# motordriver-v4_0_power-stage.net
KiCad netlist of a schematic drawn in Altium Designer
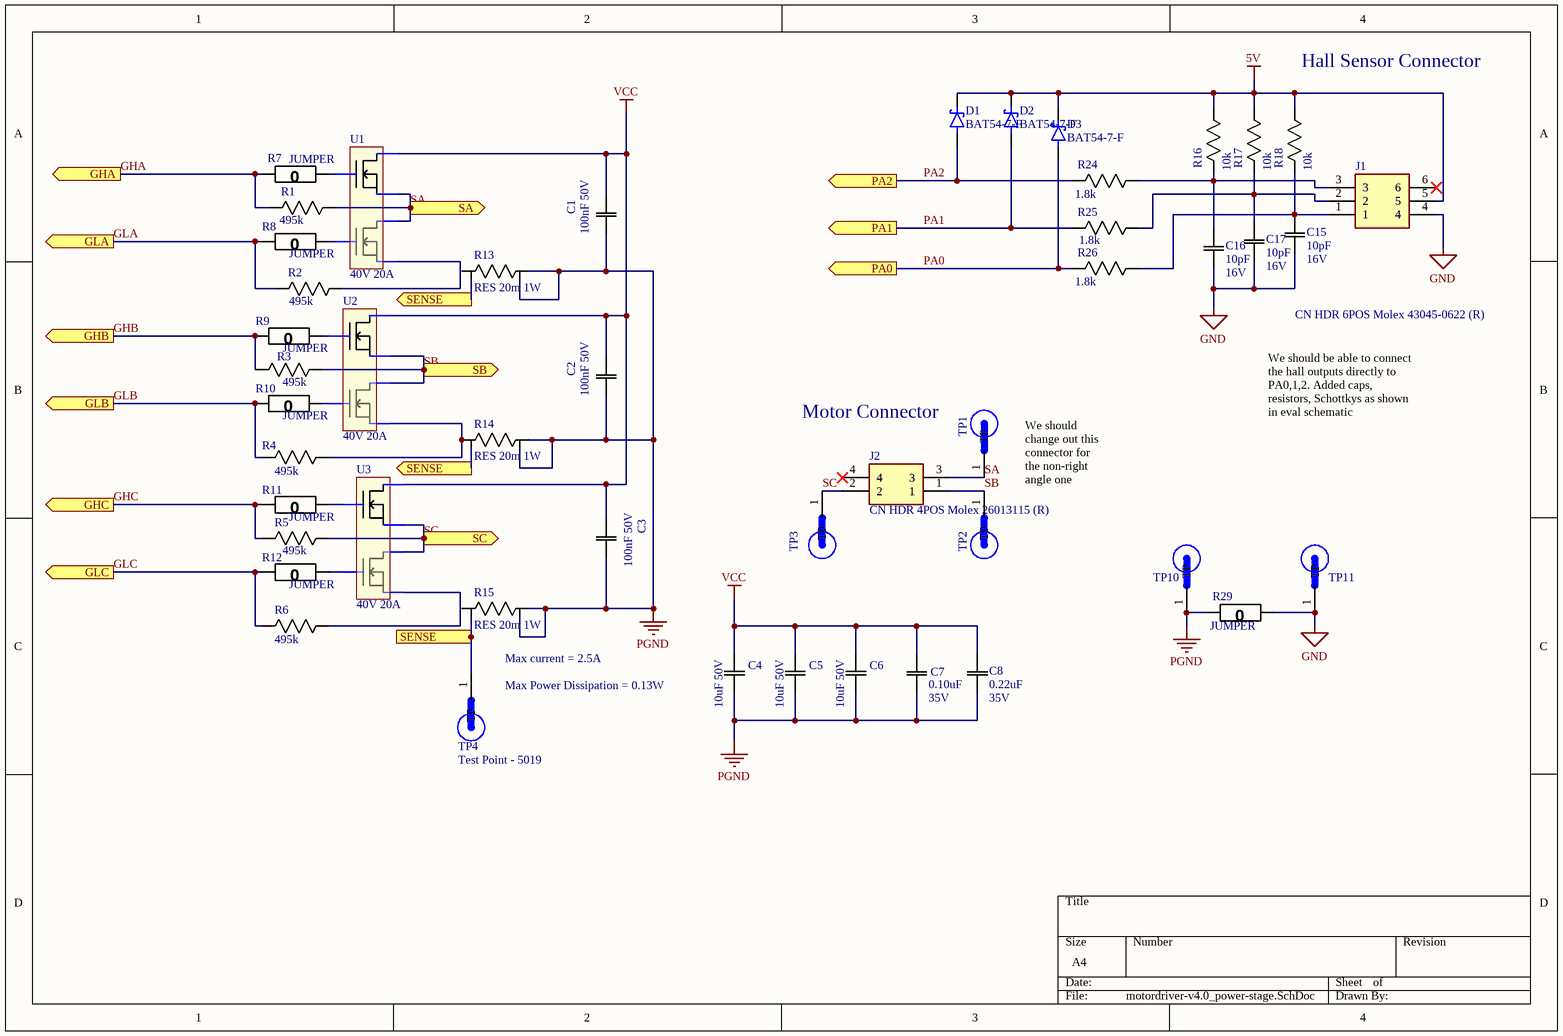
[diagram p0: motordriver-v4.0_power-stage.SchDoc]

(export (version "E")
  (design (tool "Eeschema 10.0.6"))
  (components
    (comp (ref "C1")
      (value "100nF 50V")
      (footprint "0603")
      (description "CAP CER 0.1UF 50V X7R 0805")
      (fields (field (name "TOLERANCE") "10%"))
      (libsource (lib "AltiumLibraries") (part "CAP 100nF 50V"))
    )
    (comp (ref "C2")
      (value "100nF 50V")
      (footprint "0603")
      (description "CAP CER 0.1UF 50V X7R 0805")
      (fields (field (name "TOLERANCE") "10%"))
      (libsource (lib "AltiumLibraries") (part "CAP 100nF 50V"))
    )
    (comp (ref "C3")
      (value "100nF 50V")
      (footprint "0603")
      (description "CAP CER 0.1UF 50V X7R 0805")
      (fields (field (name "TOLERANCE") "10%"))
      (libsource (lib "AltiumLibraries") (part "CAP 100nF 50V"))
    )
    (comp (ref "C4")
      (value "10uF 50V")
      (footprint "0805")
      (description "CAP CER 10UF 50V X7R")
      (fields (field (name "TOLERANCE") "10%"))
      (libsource (lib "AltiumLibraries") (part "CAP 10uF 50V"))
    )
    (comp (ref "C5")
      (value "10uF 50V")
      (footprint "0805")
      (description "CAP CER 10UF 50V X7R")
      (fields (field (name "TOLERANCE") "10%"))
      (libsource (lib "AltiumLibraries") (part "CAP 10uF 50V"))
    )
    (comp (ref "C6")
      (value "10uF 50V")
      (footprint "0805")
      (description "CAP CER 10UF 50V X7R")
      (fields (field (name "TOLERANCE") "10%"))
      (libsource (lib "AltiumLibraries") (part "CAP 10uF 50V"))
    )
    (comp (ref "C7")
      (value "0.10uF")
      (footprint "0603")
      (description "CAP CER 0.10UF 35V X7R 0603/0805")
      (fields (field (name "TOLERANCE") "10%") (field (name "RATING") "35V"))
      (libsource (lib "AltiumLibraries") (part "CAP 0.10uF 35V"))
    )
    (comp (ref "C8")
      (value "0.22uF")
      (footprint "0603")
      (description "CAP CER 0.22UF 35V X7R 0603/0805")
      (fields (field (name "TOLERANCE") "10%") (field (name "RATING") "35V"))
      (libsource (lib "AltiumLibraries") (part "CAP 0.22uF 35V"))
    )
    (comp (ref "C15")
      (value "10pF")
      (footprint "0603")
      (description "CAP CER 10PF 16V X5R 0603")
      (fields (field (name "TOLERANCE") "10%") (field (name "RATING") "16V"))
      (libsource (lib "AltiumLibraries") (part "CAP 10pF 16V"))
    )
    (comp (ref "C16")
      (value "10pF")
      (footprint "0603")
      (description "CAP CER 10PF 16V X5R 0603")
      (fields (field (name "TOLERANCE") "10%") (field (name "RATING") "16V"))
      (libsource (lib "AltiumLibraries") (part "CAP 10pF 16V"))
    )
    (comp (ref "C17")
      (value "10pF")
      (footprint "0603")
      (description "CAP CER 10PF 16V X5R 0603")
      (fields (field (name "TOLERANCE") "10%") (field (name "RATING") "16V"))
      (libsource (lib "AltiumLibraries") (part "CAP 10pF 16V"))
    )
    (comp (ref "D1")
      (value "BAT54-7-F")
      (footprint "BAT54-7-F")
      (description "DIODE SCHOTTKY 30V 200MA SOT23-3")
      (fields (field (name "MANUFACTURER") "Diodes Incorporated"))
      (libsource (lib "AltiumLibraries") (part "DIODE SCHOTTKY BAT54-7-F"))
    )
    (comp (ref "D2")
      (value "BAT54-7-F")
      (footprint "BAT54-7-F")
      (description "DIODE SCHOTTKY 30V 200MA SOT23-3")
      (fields (field (name "MANUFACTURER") "Diodes Incorporated"))
      (libsource (lib "AltiumLibraries") (part "DIODE SCHOTTKY BAT54-7-F"))
    )
    (comp (ref "D3")
      (value "BAT54-7-F")
      (footprint "BAT54-7-F")
      (description "DIODE SCHOTTKY 30V 200MA SOT23-3")
      (fields (field (name "MANUFACTURER") "Diodes Incorporated"))
      (libsource (lib "AltiumLibraries") (part "DIODE SCHOTTKY BAT54-7-F"))
    )
    (comp (ref "J1")
      (value "CN HDR 6POS Molex 43045-0622 (R)")
      (footprint "430450622")
      (description "Molex 43045-0622 6POS Microfit\r\ndual row, right angle")
      (libsource (lib "AltiumLibraries") (part "CN HDR 6POS Molex 43045-0622 (R)"))
    )
    (comp (ref "J2")
      (value "CN HDR 4POS Molex 26013115 (R)")
      (footprint "26013115")
      (description "Molex 26013115 4POS Minifit\r\ndual row, right angle")
      (libsource (lib "AltiumLibraries") (part "CN HDR 4POS Molex 26013115 (R)"))
    )
    (comp (ref "R1")
      (value "495k")
      (footprint "0603")
      (description "RES SMD 499K OHM 1% 1/8W 0805")
      (fields
        (field (name "MANUFACTURER") "Yageo")
        (field (name "MANUFACTURER PART NUMBER") "RC0805FR-07499KL")
      )
      (libsource (lib "AltiumLibraries") (part "RES 495k 1/8W"))
    )
    (comp (ref "R2")
      (value "495k")
      (footprint "0603")
      (description "RES SMD 499K OHM 1% 1/8W 0805")
      (fields
        (field (name "MANUFACTURER") "Yageo")
        (field (name "MANUFACTURER PART NUMBER") "RC0805FR-07499KL")
      )
      (libsource (lib "AltiumLibraries") (part "RES 495k 1/8W"))
    )
    (comp (ref "R3")
      (value "495k")
      (footprint "0603")
      (description "RES SMD 499K OHM 1% 1/8W 0805")
      (fields
        (field (name "MANUFACTURER") "Yageo")
        (field (name "MANUFACTURER PART NUMBER") "RC0805FR-07499KL")
      )
      (libsource (lib "AltiumLibraries") (part "RES 495k 1/8W"))
    )
    (comp (ref "R4")
      (value "495k")
      (footprint "0603")
      (description "RES SMD 499K OHM 1% 1/8W 0805")
      (fields
        (field (name "MANUFACTURER") "Yageo")
        (field (name "MANUFACTURER PART NUMBER") "RC0805FR-07499KL")
      )
      (libsource (lib "AltiumLibraries") (part "RES 495k 1/8W"))
    )
    (comp (ref "R5")
      (value "495k")
      (footprint "0603")
      (description "RES SMD 499K OHM 1% 1/8W 0805")
      (fields
        (field (name "MANUFACTURER") "Yageo")
        (field (name "MANUFACTURER PART NUMBER") "RC0805FR-07499KL")
      )
      (libsource (lib "AltiumLibraries") (part "RES 495k 1/8W"))
    )
    (comp (ref "R6")
      (value "495k")
      (footprint "0603")
      (description "RES SMD 499K OHM 1% 1/8W 0805")
      (fields
        (field (name "MANUFACTURER") "Yageo")
        (field (name "MANUFACTURER PART NUMBER") "RC0805FR-07499KL")
      )
      (libsource (lib "AltiumLibraries") (part "RES 495k 1/8W"))
    )
    (comp (ref "R7")
      (value "JUMPER")
      (footprint "0603")
      (description "RES SMD 0 OHM JUMPER GENERIC 0805")
      (libsource (lib "AltiumLibraries") (part "RES 0 JUMPER"))
    )
    (comp (ref "R8")
      (value "JUMPER")
      (footprint "0603")
      (description "RES SMD 0 OHM JUMPER GENERIC 0805")
      (libsource (lib "AltiumLibraries") (part "RES 0 JUMPER"))
    )
    (comp (ref "R9")
      (value "JUMPER")
      (footprint "0603")
      (description "RES SMD 0 OHM JUMPER GENERIC 0805")
      (libsource (lib "AltiumLibraries") (part "RES 0 JUMPER"))
    )
    (comp (ref "R10")
      (value "JUMPER")
      (footprint "0603")
      (description "RES SMD 0 OHM JUMPER GENERIC 0805")
      (libsource (lib "AltiumLibraries") (part "RES 0 JUMPER"))
    )
    (comp (ref "R11")
      (value "JUMPER")
      (footprint "0603")
      (description "RES SMD 0 OHM JUMPER GENERIC 0805")
      (libsource (lib "AltiumLibraries") (part "RES 0 JUMPER"))
    )
    (comp (ref "R12")
      (value "JUMPER")
      (footprint "0603")
      (description "RES SMD 0 OHM JUMPER GENERIC 0805")
      (libsource (lib "AltiumLibraries") (part "RES 0 JUMPER"))
    )
    (comp (ref "R13")
      (value "RES 20m 1W")
      (footprint "1206 - Sense")
      (description "RES SMD 0.02 OHM 1% 1W 1206")
      (libsource (lib "AltiumLibraries") (part "RES 20m 1W"))
    )
    (comp (ref "R14")
      (value "RES 20m 1W")
      (footprint "1206 - Sense")
      (description "RES SMD 0.02 OHM 1% 1W 1206")
      (libsource (lib "AltiumLibraries") (part "RES 20m 1W"))
    )
    (comp (ref "R15")
      (value "RES 20m 1W")
      (footprint "1206 - Sense")
      (description "RES SMD 0.02 OHM 1% 1W 1206")
      (libsource (lib "AltiumLibraries") (part "RES 20m 1W"))
    )
    (comp (ref "R16")
      (value "10k")
      (footprint "0603")
      (description "RES SMD 10K OHM 1% 1/8W 0805")
      (fields (field (name "TOLERANCE") "1%"))
      (libsource (lib "AltiumLibraries") (part "RES 10k 1/8W - 1%"))
    )
    (comp (ref "R17")
      (value "10k")
      (footprint "0603")
      (description "RES SMD 10K OHM 1% 1/8W 0805")
      (fields (field (name "TOLERANCE") "1%"))
      (libsource (lib "") (part "RES 10k 1/8W - 1%_1"))
    )
    (comp (ref "R18")
      (value "10k")
      (footprint "0603")
      (description "RES SMD 10K OHM 1% 1/8W 0805")
      (fields (field (name "TOLERANCE") "1%"))
      (libsource (lib "") (part "RES 10k 1/8W - 1%_1"))
    )
    (comp (ref "R24")
      (value "1.8k")
      (footprint "0603")
      (description "RES SMD 1.8K OHM 5% 1/8W 0805")
      (fields (field (name "TOLERANCE") "5%"))
      (libsource (lib "AltiumLibraries") (part "RES 1.8k 1/8W"))
    )
    (comp (ref "R25")
      (value "1.8k")
      (footprint "0603")
      (description "RES SMD 1.8K OHM 5% 1/8W 0805")
      (fields (field (name "TOLERANCE") "5%"))
      (libsource (lib "AltiumLibraries") (part "RES 1.8k 1/8W"))
    )
    (comp (ref "R26")
      (value "1.8k")
      (footprint "0603")
      (description "RES SMD 1.8K OHM 5% 1/8W 0805")
      (fields (field (name "TOLERANCE") "5%"))
      (libsource (lib "AltiumLibraries") (part "RES 1.8k 1/8W"))
    )
    (comp (ref "R29")
      (value "JUMPER")
      (footprint "0603")
      (description "RES SMD 0 OHM JUMPER GENERIC 0805")
      (libsource (lib "AltiumLibraries") (part "RES 0 JUMPER"))
    )
    (comp (ref "TP1")
      (value "Test Point - 5019")
      (footprint "TP380X203")
      (description "PC Test Point, Miniature Phosphor Bronze, Silver Plating Surface Mount Mounting Type")
      (fields (field (name "MP") "5019") (field (name "MF") "Keystone Electronics"))
      (libsource (lib "AltiumLibraries") (part "Test Point - 5019"))
    )
    (comp (ref "TP2")
      (value "Test Point - 5019")
      (footprint "TP380X203")
      (description "PC Test Point, Miniature Phosphor Bronze, Silver Plating Surface Mount Mounting Type")
      (fields (field (name "MP") "5019") (field (name "MF") "Keystone Electronics"))
      (libsource (lib "AltiumLibraries") (part "Test Point - 5019"))
    )
    (comp (ref "TP3")
      (value "Test Point - 5019")
      (footprint "TP380X203")
      (description "PC Test Point, Miniature Phosphor Bronze, Silver Plating Surface Mount Mounting Type")
      (fields (field (name "MP") "5019") (field (name "MF") "Keystone Electronics"))
      (libsource (lib "AltiumLibraries") (part "Test Point - 5019"))
    )
    (comp (ref "TP4")
      (value "Test Point - 5019")
      (footprint "TP380X203")
      (description "PC Test Point, Miniature Phosphor Bronze, Silver Plating Surface Mount Mounting Type")
      (fields (field (name "MP") "5019") (field (name "MF") "Keystone Electronics"))
      (libsource (lib "AltiumLibraries") (part "Test Point - 5019"))
    )
    (comp (ref "TP10")
      (value "Test Point - 5019")
      (footprint "TP380X203")
      (description "PC Test Point, Miniature Phosphor Bronze, Silver Plating Surface Mount Mounting Type")
      (fields (field (name "MP") "5019") (field (name "MF") "Keystone Electronics"))
      (libsource (lib "AltiumLibraries") (part "Test Point - 5019"))
    )
    (comp (ref "TP11")
      (value "Test Point - 5019")
      (footprint "TP380X203")
      (description "PC Test Point, Miniature Phosphor Bronze, Silver Plating Surface Mount Mounting Type")
      (fields (field (name "MP") "5019") (field (name "MF") "Keystone Electronics"))
      (libsource (lib "AltiumLibraries") (part "Test Point - 5019"))
    )
    (comp (ref "U1")
      (value "40V 20A")
      (footprint "PowerPAK SO8 Dual")
      (description "MOSFET N+N 40V 20A")
      (fields (field (name "MF") "Vishay Siliconix"))
      (libsource (lib "AltiumLibraries") (part "MOSFET N-CH DUAL 40V 20A"))
    )
    (comp (ref "U2")
      (value "40V 20A")
      (footprint "PowerPAK SO8 Dual")
      (description "MOSFET N+N 40V 20A")
      (fields (field (name "MF") "Vishay Siliconix"))
      (libsource (lib "AltiumLibraries") (part "MOSFET N-CH DUAL 40V 20A"))
    )
    (comp (ref "U3")
      (value "40V 20A")
      (footprint "PowerPAK SO8 Dual")
      (description "MOSFET N+N 40V 20A")
      (fields (field (name "MF") "Vishay Siliconix"))
      (libsource (lib "AltiumLibraries") (part "MOSFET N-CH DUAL 40V 20A"))
    )
  )
  (nets
    (net (code "1") (name "/GHA") (class "Default")
      (node (ref "R1") (pin "2") (pinfunction "R2_2") (pintype "passive"))
      (node (ref "R7") (pin "2") (pinfunction "R2_2") (pintype "passive"))
    )
    (net (code "2") (name "/GHB") (class "Default")
      (node (ref "R3") (pin "2") (pinfunction "R2_2") (pintype "passive"))
      (node (ref "R9") (pin "2") (pinfunction "R2_2") (pintype "passive"))
    )
    (net (code "3") (name "/GHC") (class "Default")
      (node (ref "R11") (pin "2") (pinfunction "R2_2") (pintype "passive"))
      (node (ref "R5") (pin "2") (pinfunction "R2_2") (pintype "passive"))
    )
    (net (code "4") (name "/GLA") (class "Default")
      (node (ref "R2") (pin "2") (pinfunction "R2_2") (pintype "passive"))
      (node (ref "R8") (pin "2") (pinfunction "R2_2") (pintype "passive"))
    )
    (net (code "5") (name "/GLB") (class "Default")
      (node (ref "R10") (pin "2") (pinfunction "R2_2") (pintype "passive"))
      (node (ref "R4") (pin "2") (pinfunction "R2_2") (pintype "passive"))
    )
    (net (code "6") (name "/GLC") (class "Default")
      (node (ref "R12") (pin "2") (pinfunction "R2_2") (pintype "passive"))
      (node (ref "R6") (pin "2") (pinfunction "R2_2") (pintype "passive"))
    )
    (net (code "7") (name "/PA0") (class "Default")
      (node (ref "D3") (pin "1") (pinfunction "A_1") (pintype "passive"))
      (node (ref "R26") (pin "2") (pinfunction "R2_2") (pintype "passive"))
    )
    (net (code "8") (name "/PA1") (class "Default")
      (node (ref "D2") (pin "1") (pinfunction "A_1") (pintype "passive"))
      (node (ref "R25") (pin "2") (pinfunction "R2_2") (pintype "passive"))
    )
    (net (code "9") (name "/PA2") (class "Default")
      (node (ref "D1") (pin "1") (pinfunction "A_1") (pintype "passive"))
      (node (ref "R24") (pin "2") (pinfunction "R2_2") (pintype "passive"))
    )
    (net (code "10") (name "/SA") (class "Default")
      (node (ref "J2") (pin "3") (pinfunction "3_3") (pintype "passive"))
      (node (ref "R1") (pin "1") (pinfunction "R1_1") (pintype "passive"))
      (node (ref "TP1") (pin "1") (pinfunction "TP_1") (pintype "passive"))
      (node (ref "U1") (pin "1") (pinfunction "S1_1") (pintype "passive"))
      (node (ref "U1") (pin "6") (pinfunction "D2_6") (pintype "passive"))
    )
    (net (code "11") (name "/SB") (class "Default")
      (node (ref "J2") (pin "1") (pinfunction "1_1") (pintype "passive"))
      (node (ref "R3") (pin "1") (pinfunction "R1_1") (pintype "passive"))
      (node (ref "TP2") (pin "1") (pinfunction "TP_1") (pintype "passive"))
      (node (ref "U2") (pin "1") (pinfunction "S1_1") (pintype "passive"))
      (node (ref "U2") (pin "6") (pinfunction "D2_6") (pintype "passive"))
    )
    (net (code "12") (name "/SC") (class "Default")
      (node (ref "J2") (pin "2") (pinfunction "2_2") (pintype "passive"))
      (node (ref "R5") (pin "1") (pinfunction "R1_1") (pintype "passive"))
      (node (ref "TP3") (pin "1") (pinfunction "TP_1") (pintype "passive"))
      (node (ref "U3") (pin "1") (pinfunction "S1_1") (pintype "passive"))
      (node (ref "U3") (pin "6") (pinfunction "D2_6") (pintype "passive"))
    )
    (net (code "13") (name "/SENSE") (class "Default")
      (node (ref "R13") (pin "3") (pinfunction "3_3") (pintype "passive"))
      (node (ref "R14") (pin "3") (pinfunction "3_3") (pintype "passive"))
      (node (ref "R15") (pin "3") (pinfunction "3_3") (pintype "passive"))
      (node (ref "TP4") (pin "1") (pinfunction "TP_1") (pintype "passive"))
    )
    (net (code "14") (name "5V") (class "Default")
      (node (ref "D1") (pin "3") (pinfunction "K_3") (pintype "passive"))
      (node (ref "D2") (pin "3") (pinfunction "K_3") (pintype "passive"))
      (node (ref "D3") (pin "3") (pinfunction "K_3") (pintype "passive"))
      (node (ref "J1") (pin "5") (pinfunction "5_5") (pintype "passive"))
      (node (ref "R16") (pin "1") (pinfunction "R1_1") (pintype "passive"))
      (node (ref "R17") (pin "1") (pinfunction "R1_1") (pintype "passive"))
      (node (ref "R18") (pin "1") (pinfunction "R1_1") (pintype "passive"))
    )
    (net (code "15") (name "GND") (class "Default")
      (node (ref "C15") (pin "1") (pinfunction "C1_1") (pintype "passive"))
      (node (ref "C16") (pin "1") (pinfunction "C1_1") (pintype "passive"))
      (node (ref "C17") (pin "1") (pinfunction "C1_1") (pintype "passive"))
      (node (ref "J1") (pin "4") (pinfunction "4_4") (pintype "passive"))
      (node (ref "R29") (pin "1") (pinfunction "R1_1") (pintype "passive"))
      (node (ref "TP11") (pin "1") (pinfunction "TP_1") (pintype "passive"))
    )
    (net (code "16") (name "Net-(C15-C2)") (class "Default")
      (node (ref "C15") (pin "2") (pinfunction "C2_2") (pintype "passive"))
      (node (ref "J1") (pin "1") (pinfunction "1_1") (pintype "passive"))
      (node (ref "R18") (pin "2") (pinfunction "R2_2") (pintype "passive"))
      (node (ref "R26") (pin "1") (pinfunction "R1_1") (pintype "passive"))
    )
    (net (code "17") (name "Net-(C16-C2)") (class "Default")
      (node (ref "C16") (pin "2") (pinfunction "C2_2") (pintype "passive"))
      (node (ref "J1") (pin "3") (pinfunction "3_3") (pintype "passive"))
      (node (ref "R16") (pin "2") (pinfunction "R2_2") (pintype "passive"))
      (node (ref "R24") (pin "1") (pinfunction "R1_1") (pintype "passive"))
    )
    (net (code "18") (name "Net-(C17-C2)") (class "Default")
      (node (ref "C17") (pin "2") (pinfunction "C2_2") (pintype "passive"))
      (node (ref "J1") (pin "2") (pinfunction "2_2") (pintype "passive"))
      (node (ref "R17") (pin "2") (pinfunction "R2_2") (pintype "passive"))
      (node (ref "R25") (pin "1") (pinfunction "R1_1") (pintype "passive"))
    )
    (net (code "19") (name "Net-(R2-R1)") (class "Default")
      (node (ref "R2") (pin "1") (pinfunction "R1_1") (pintype "passive"))
      (node (ref "U1") (pin "3") (pinfunction "S2_3") (pintype "passive"))
    )
    (net (code "20") (name "Net-(R6-R1)") (class "Default")
      (node (ref "R6") (pin "1") (pinfunction "R1_1") (pintype "passive"))
      (node (ref "U3") (pin "3") (pinfunction "S2_3") (pintype "passive"))
    )
    (net (code "21") (name "Net-(R7-R1)") (class "Default")
      (node (ref "R7") (pin "1") (pinfunction "R1_1") (pintype "passive"))
      (node (ref "U1") (pin "2") (pinfunction "G1_2") (pintype "passive"))
    )
    (net (code "22") (name "Net-(R8-R1)") (class "Default")
      (node (ref "R8") (pin "1") (pinfunction "R1_1") (pintype "passive"))
      (node (ref "U1") (pin "4") (pinfunction "G2_4") (pintype "passive"))
    )
    (net (code "23") (name "Net-(R9-R1)") (class "Default")
      (node (ref "R9") (pin "1") (pinfunction "R1_1") (pintype "passive"))
      (node (ref "U2") (pin "2") (pinfunction "G1_2") (pintype "passive"))
    )
    (net (code "24") (name "Net-(R10-R1)") (class "Default")
      (node (ref "R10") (pin "1") (pinfunction "R1_1") (pintype "passive"))
      (node (ref "U2") (pin "4") (pinfunction "G2_4") (pintype "passive"))
    )
    (net (code "25") (name "Net-(R11-R1)") (class "Default")
      (node (ref "R11") (pin "1") (pinfunction "R1_1") (pintype "passive"))
      (node (ref "U3") (pin "2") (pinfunction "G1_2") (pintype "passive"))
    )
    (net (code "26") (name "Net-(R12-R1)") (class "Default")
      (node (ref "R12") (pin "1") (pinfunction "R1_1") (pintype "passive"))
      (node (ref "U3") (pin "4") (pinfunction "G2_4") (pintype "passive"))
    )
    (net (code "27") (name "Net-(R14-R1)") (class "Default")
      (node (ref "R14") (pin "1") (pinfunction "R1_1") (pintype "passive"))
      (node (ref "R4") (pin "1") (pinfunction "R1_1") (pintype "passive"))
      (node (ref "U2") (pin "3") (pinfunction "S2_3") (pintype "passive"))
    )
    (net (code "28") (name "PGND") (class "Default")
      (node (ref "C1") (pin "1") (pinfunction "C1_1") (pintype "passive"))
      (node (ref "C2") (pin "1") (pinfunction "C1_1") (pintype "passive"))
      (node (ref "C3") (pin "1") (pinfunction "C1_1") (pintype "passive"))
      (node (ref "C4") (pin "2") (pinfunction "C2_2") (pintype "passive"))
      (node (ref "C5") (pin "2") (pinfunction "C2_2") (pintype "passive"))
      (node (ref "C6") (pin "2") (pinfunction "C2_2") (pintype "passive"))
      (node (ref "C7") (pin "1") (pinfunction "C1_1") (pintype "passive"))
      (node (ref "C8") (pin "1") (pinfunction "C1_1") (pintype "passive"))
      (node (ref "R13") (pin "2") (pinfunction "R2_2") (pintype "passive"))
      (node (ref "R13") (pin "4") (pinfunction "4_4") (pintype "passive"))
      (node (ref "R14") (pin "2") (pinfunction "R2_2") (pintype "passive"))
      (node (ref "R14") (pin "4") (pinfunction "4_4") (pintype "passive"))
      (node (ref "R15") (pin "2") (pinfunction "R2_2") (pintype "passive"))
      (node (ref "R15") (pin "4") (pinfunction "4_4") (pintype "passive"))
      (node (ref "R29") (pin "2") (pinfunction "R2_2") (pintype "passive"))
      (node (ref "TP10") (pin "1") (pinfunction "TP_1") (pintype "passive"))
    )
    (net (code "29") (name "VCC") (class "Default")
      (node (ref "C1") (pin "2") (pinfunction "C2_2") (pintype "passive"))
      (node (ref "C2") (pin "2") (pinfunction "C2_2") (pintype "passive"))
      (node (ref "C3") (pin "2") (pinfunction "C2_2") (pintype "passive"))
      (node (ref "C4") (pin "1") (pinfunction "C1_1") (pintype "passive"))
      (node (ref "C5") (pin "1") (pinfunction "C1_1") (pintype "passive"))
      (node (ref "C6") (pin "1") (pinfunction "C1_1") (pintype "passive"))
      (node (ref "C7") (pin "2") (pinfunction "C2_2") (pintype "passive"))
      (node (ref "C8") (pin "2") (pinfunction "C2_2") (pintype "passive"))
      (node (ref "U1") (pin "8") (pinfunction "D1_8") (pintype "passive"))
      (node (ref "U2") (pin "8") (pinfunction "D1_8") (pintype "passive"))
      (node (ref "U3") (pin "8") (pinfunction "D1_8") (pintype "passive"))
    )
    (net (code "30") (name "unconnected-(J1-Pad6)") (class "Default")
      (node (ref "J1") (pin "6") (pinfunction "6_6") (pintype "passive+no_connect"))
    )
    (net (code "31") (name "unconnected-(J2-Pad4)") (class "Default")
      (node (ref "J2") (pin "4") (pinfunction "4_4") (pintype "passive+no_connect"))
    )
    (net (code "32") (name "unconnected-(R13-R1-Pad1)") (class "Default")
      (node (ref "R13") (pin "1") (pinfunction "R1_1") (pintype "passive"))
    )
    (net (code "33") (name "unconnected-(R15-R1-Pad1)") (class "Default")
      (node (ref "R15") (pin "1") (pinfunction "R1_1") (pintype "passive"))
    )
  )
)
